# Wireless_Master.net
KiCad netlist of a schematic drawn in Altium Designer
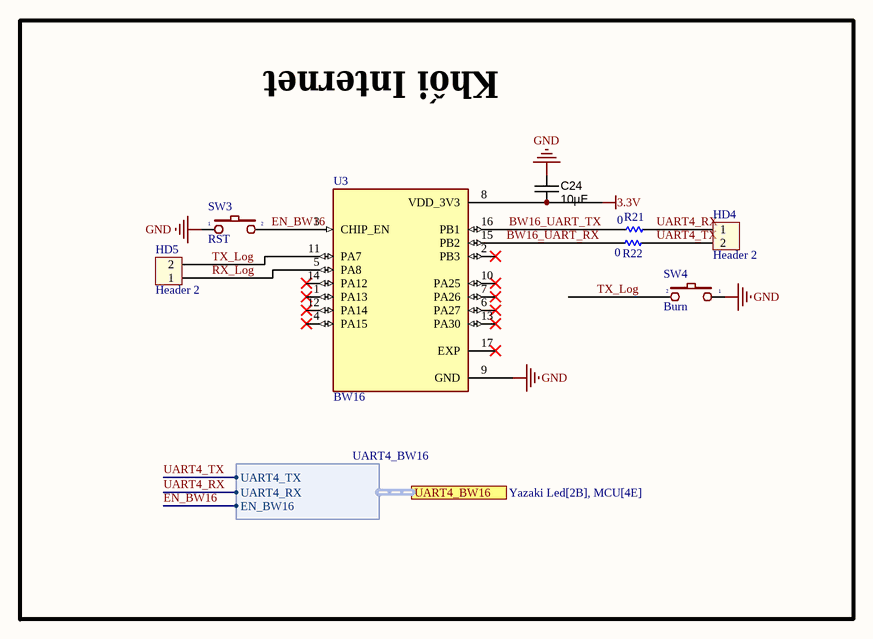
[diagram p0: Wireless_Master.SchDoc]

(export (version "E")
  (design (tool "Eeschema 10.0.6"))
  (components
    (comp (ref "C24")
      (value "10µF")
      (footprint "CAPC1608X90N")
      (description "1µF ±10% 16V Ceramic Capacitor X7R 0603 (1608 Metric)")
      (fields (field (name "TOLERANCE") "±10%"))
      (libsource (lib "All Library") (part "CAPC_1uF_0603_X7R_35V_10%"))
    )
    (comp (ref "HD4") (value "Header 2") (footprint "Header_2") (libsource (lib "lpson") (part "Header2")))
    (comp (ref "HD5") (value "Header 2") (footprint "Header_2") (libsource (lib "") (part "Header2_1")))
    (comp (ref "R21")
      (value "0")
      (footprint "RES-SMD-0603")
      (description "Resistor")
      (fields
        (field (name "MANUFACTURER") "Generic Components")
        (field (name "PUBLISHER") "Altium Hobart Technology Centre")
      )
      (libsource (lib "thu vien 3d") (part "Res-SMD"))
    )
    (comp (ref "R22")
      (value "0")
      (footprint "RES-SMD-0603")
      (description "Resistor")
      (fields
        (field (name "MANUFACTURER") "Generic Components")
        (field (name "PUBLISHER") "Altium Hobart Technology Centre")
      )
      (libsource (lib "thu vien 3d") (part "Res-SMD"))
    )
    (comp (ref "SW3")
      (value "RST")
      (footprint "SW1-SMD")
      (description "Switch button 2 pin")
      (libsource (lib "thu vien 3d") (part "SW2"))
    )
    (comp (ref "SW4")
      (value "Burn")
      (footprint "SW1-SMD")
      (description "Switch button 2 pin")
      (libsource (lib "Library Led Yazaki") (part "SW2"))
    )
    (comp (ref "U3")
      (value "BW16")
      (footprint "MODULE_BW16")
      (description "dual-frequency Wi-Fi Bluetooth SoC module")
      (fields (field (name "MF") "AI-Thinker"))
      (libsource (lib "BW16") (part "BW16"))
    )
  )
  (nets
    (net (code "2") (name "/BW16_UART_RX") (class "Default")
      (node (ref "R22") (pin "2") (pinfunction "2_2") (pintype "passive"))
      (node (ref "U3") (pin "15") (pinfunction "PB2_15") (pintype "bidirectional"))
    )
    (net (code "3") (name "/BW16_UART_TX") (class "Default")
      (node (ref "R21") (pin "2") (pinfunction "2_2") (pintype "passive"))
      (node (ref "U3") (pin "16") (pinfunction "PB1_16") (pintype "bidirectional"))
    )
    (net (code "4") (name "/EN_BW16") (class "Default")
      (node (ref "SW3") (pin "2") (pinfunction "2_2") (pintype "passive"))
      (node (ref "U3") (pin "3") (pinfunction "CHIP_EN_3") (pintype "input"))
    )
    (net (code "5") (name "/RX_Log") (class "Default")
      (node (ref "HD5") (pin "1") (pinfunction "1_1") (pintype "passive"))
      (node (ref "U3") (pin "5") (pinfunction "PA8_5") (pintype "bidirectional"))
    )
    (net (code "6") (name "/TX_Log") (class "Default")
      (node (ref "HD5") (pin "2") (pinfunction "2_2") (pintype "passive"))
      (node (ref "SW4") (pin "2") (pinfunction "2_2") (pintype "passive"))
      (node (ref "U3") (pin "11") (pinfunction "PA7_11") (pintype "bidirectional"))
    )
    (net (code "7") (name "/UART4_RX") (class "Default")
      (node (ref "HD4") (pin "1") (pinfunction "1_1") (pintype "passive"))
      (node (ref "R21") (pin "1") (pinfunction "1_1") (pintype "passive"))
    )
    (net (code "8") (name "/UART4_TX") (class "Default")
      (node (ref "HD4") (pin "2") (pinfunction "2_2") (pintype "passive"))
      (node (ref "R22") (pin "1") (pinfunction "1_1") (pintype "passive"))
    )
    (net (code "10") (name "3.3V") (class "Default")
      (node (ref "C24") (pin "1") (pintype "passive"))
      (node (ref "U3") (pin "8") (pinfunction "VDD_3V3_8") (pintype "power_in"))
    )
    (net (code "11") (name "GND") (class "Default")
      (node (ref "C24") (pin "2") (pintype "passive"))
      (node (ref "SW3") (pin "1") (pinfunction "1_1") (pintype "passive"))
      (node (ref "SW4") (pin "1") (pinfunction "1_1") (pintype "passive"))
      (node (ref "U3") (pin "9") (pinfunction "GND_9") (pintype "power_in"))
    )
    (net (code "12") (name "unconnected-(U3-EXP-Pad17)") (class "Default")
      (node (ref "U3") (pin "17") (pinfunction "EXP_17") (pintype "passive+no_connect"))
    )
    (net (code "13") (name "unconnected-(U3-PA12-Pad14)") (class "Default")
      (node (ref "U3") (pin "14") (pinfunction "PA12_14") (pintype "bidirectional+no_connect"))
    )
    (net (code "14") (name "unconnected-(U3-PA13-Pad1)") (class "Default")
      (node (ref "U3") (pin "1") (pinfunction "PA13_1") (pintype "bidirectional+no_connect"))
    )
    (net (code "15") (name "unconnected-(U3-PA14-Pad12)") (class "Default")
      (node (ref "U3") (pin "12") (pinfunction "PA14_12") (pintype "bidirectional+no_connect"))
    )
    (net (code "16") (name "unconnected-(U3-PA15-Pad4)") (class "Default")
      (node (ref "U3") (pin "4") (pinfunction "PA15_4") (pintype "bidirectional+no_connect"))
    )
    (net (code "17") (name "unconnected-(U3-PA25-Pad10)") (class "Default")
      (node (ref "U3") (pin "10") (pinfunction "PA25_10") (pintype "bidirectional+no_connect"))
    )
    (net (code "18") (name "unconnected-(U3-PA26-Pad7)") (class "Default")
      (node (ref "U3") (pin "7") (pinfunction "PA26_7") (pintype "bidirectional+no_connect"))
    )
    (net (code "19") (name "unconnected-(U3-PA27-Pad6)") (class "Default")
      (node (ref "U3") (pin "6") (pinfunction "PA27_6") (pintype "bidirectional+no_connect"))
    )
    (net (code "20") (name "unconnected-(U3-PA30-Pad13)") (class "Default")
      (node (ref "U3") (pin "13") (pinfunction "PA30_13") (pintype "bidirectional+no_connect"))
    )
    (net (code "21") (name "unconnected-(U3-PB3-Pad2)") (class "Default")
      (node (ref "U3") (pin "2") (pinfunction "PB3_2") (pintype "bidirectional+no_connect"))
    )
  )
)
